# SH10_-_OMAP-L137_JTAG.net
KiCad netlist of a schematic drawn in Altium Designer
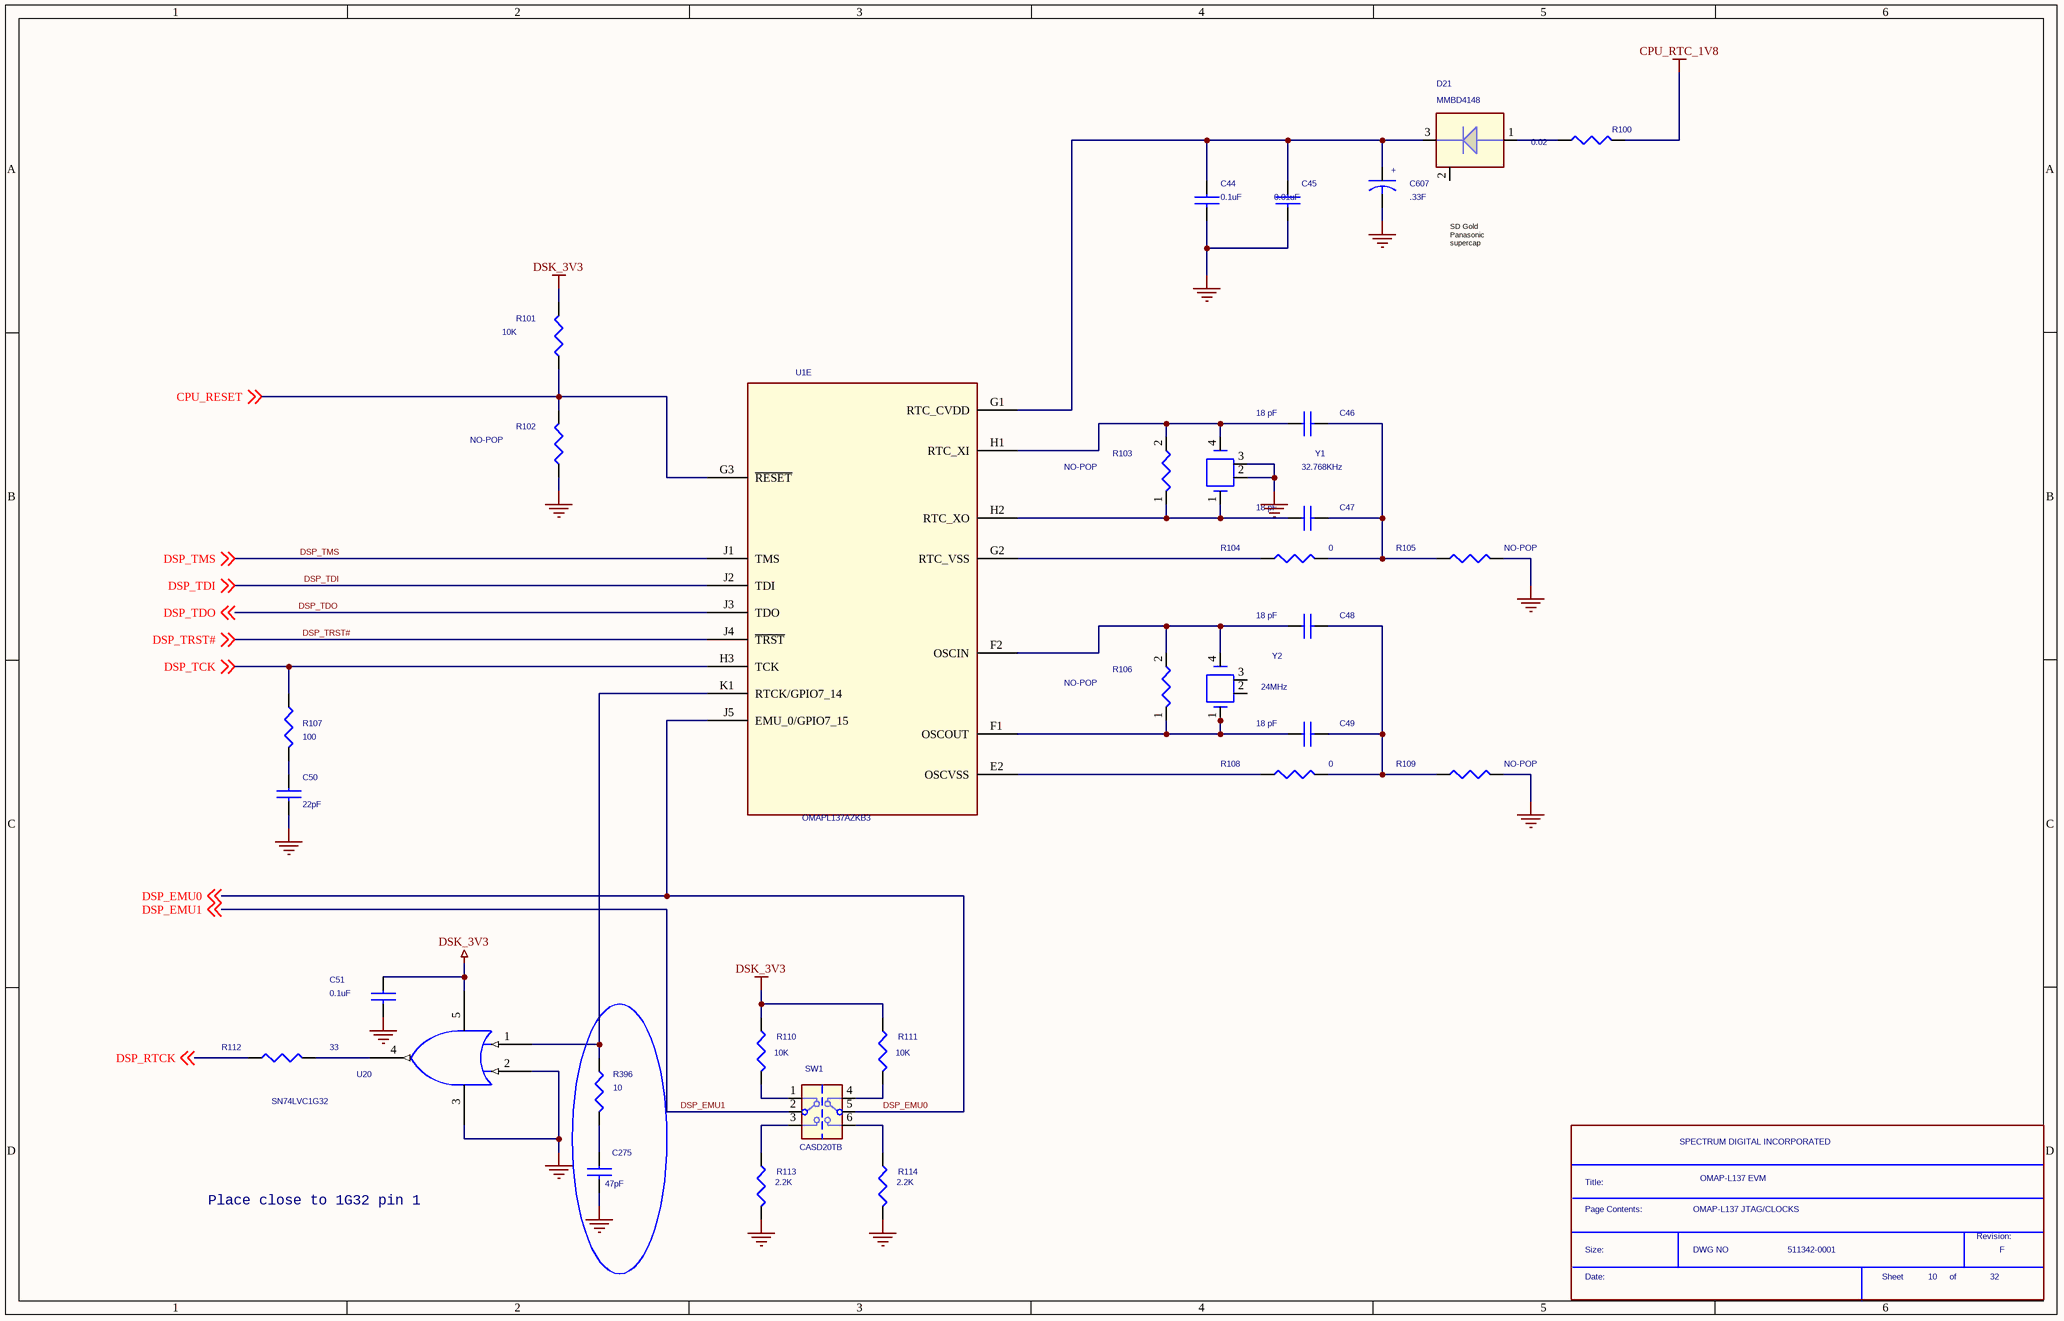
[diagram p0: SH10 - OMAP-L137 JTAG.SchDoc]

(export (version "E")
  (design (tool "Eeschema 10.0.6"))
  (components
    (comp (ref "C44")
      (value "0.1uF")
      (footprint "c402-25")
      (fields (field (name "PART #") "101587-1100R"))
      (libsource (lib "*") (part "CAP NP"))
    )
    (comp (ref "C45")
      (value "0.01uF")
      (footprint "c402-25")
      (fields (field (name "PART #") "101587-1101R"))
      (libsource (lib "*") (part "CAP NP"))
    )
    (comp (ref "C46")
      (value "18 pF")
      (footprint "c603-35x45")
      (fields (field (name "PART #") "101103-1184R"))
      (libsource (lib "*") (part "CAP NP_3"))
    )
    (comp (ref "C47")
      (value "18 pF")
      (footprint "c603-35x45")
      (fields (field (name "PART #") "101103-1184R"))
      (libsource (lib "*") (part "CAP NP_3"))
    )
    (comp (ref "C48")
      (value "18 pF")
      (footprint "c603-35x45")
      (fields (field (name "PART #") "101103-1184R"))
      (libsource (lib "*") (part "CAP NP_3"))
    )
    (comp (ref "C49")
      (value "18 pF")
      (footprint "c603-35x45")
      (fields (field (name "PART #") "101103-1184R"))
      (libsource (lib "*") (part "CAP NP_3"))
    )
    (comp (ref "C50")
      (value "22pF")
      (footprint "c603-35x45")
      (fields (field (name "PART #") "101002-1224R"))
      (libsource (lib "*") (part "CAP NP_7"))
    )
    (comp (ref "C51")
      (value "0.1uF")
      (footprint "c402-25")
      (fields (field (name "PART #") "101587-1100R"))
      (libsource (lib "*") (part "CAP NP"))
    )
    (comp (ref "C275")
      (value "47pF")
      (footprint "C0603")
      (fields (field (name "PART #") "101782-1474R"))
      (libsource (lib "*") (part "CAP .1 uF 10% 0603"))
    )
    (comp (ref "C607")
      (value ".33F")
      (footprint "EIA_D")
      (description ".33F 5.5V Gold SD Horizontal Cap.")
      (fields (field (name "MFR") "Panasonic") (field (name "PART #") "101056-0335R"))
      (libsource (lib "*") (part "CAP_0"))
    )
    (comp (ref "D21")
      (value "MMBD4148")
      (footprint "SOT23-3")
      (fields (field (name "PART #") "100185-0001R"))
      (libsource (lib "*") (part "MMBD4148_0"))
    )
    (comp (ref "R100")
      (value "0.02")
      (footprint "r1206-40x70")
      (fields (field (name "PART #") "102598-0002R"))
      (libsource (lib "*") (part "R"))
    )
    (comp (ref "R101")
      (value "10K")
      (footprint "r402-25")
      (fields (field (name "PART #") "101370-1003R"))
      (libsource (lib "*") (part "R"))
    )
    (comp (ref "R102")
      (value "NO-POP")
      (footprint "r402-25")
      (fields (field (name "PART #") "R0402-NOPOP"))
      (libsource (lib "*") (part "R"))
    )
    (comp (ref "R103")
      (value "NO-POP")
      (footprint "r402-25")
      (fields (field (name "PART #") "R0402-NOPOP"))
      (libsource (lib "*") (part "R_2"))
    )
    (comp (ref "R104")
      (value "0")
      (footprint "r402-25")
      (fields (field (name "PART #") "101370-0001R"))
      (libsource (lib "*") (part "R"))
    )
    (comp (ref "R105")
      (value "NO-POP")
      (footprint "r402-25")
      (fields (field (name "PART #") "R0402-NOPOP"))
      (libsource (lib "*") (part "R"))
    )
    (comp (ref "R106")
      (value "NO-POP")
      (footprint "r402-25")
      (fields (field (name "PART #") "R0402-NOPOP"))
      (libsource (lib "*") (part "R_2"))
    )
    (comp (ref "R107")
      (value "100")
      (footprint "r603-35x45")
      (fields (field (name "PART #") "100642-1001R"))
      (libsource (lib "*") (part "R"))
    )
    (comp (ref "R108")
      (value "0")
      (footprint "r402-25")
      (fields (field (name "PART #") "101370-0001R"))
      (libsource (lib "*") (part "R"))
    )
    (comp (ref "R109")
      (value "NO-POP")
      (footprint "r402-25")
      (fields (field (name "PART #") "R0402-NOPOP"))
      (libsource (lib "*") (part "R"))
    )
    (comp (ref "R110")
      (value "10K")
      (footprint "r402-25")
      (fields (field (name "PART #") "101370-1003R"))
      (libsource (lib "*") (part "R"))
    )
    (comp (ref "R111")
      (value "10K")
      (footprint "r402-25")
      (fields (field (name "PART #") "101370-1003R"))
      (libsource (lib "*") (part "R"))
    )
    (comp (ref "R112")
      (value "33")
      (footprint "r402-25")
      (fields (field (name "PART #") "101370-3300R"))
      (libsource (lib "*") (part "R"))
    )
    (comp (ref "R113")
      (value "2.2K")
      (footprint "r402-25")
      (fields (field (name "PART #") "101370-2202R"))
      (libsource (lib "*") (part "R"))
    )
    (comp (ref "R114")
      (value "2.2K")
      (footprint "r402-25")
      (fields (field (name "PART #") "101370-2202R"))
      (libsource (lib "*") (part "R"))
    )
    (comp (ref "R396")
      (value "10")
      (footprint "r402-25")
      (fields (field (name "PART #") "101370-1000R"))
      (libsource (lib "*") (part "R"))
    )
    (comp (ref "SW1")
      (value "CASD20TB")
      (footprint "sw6-40x67_gw")
      (description "SLIDE Switch, DPDT,  100mA, J HOOK")
      (fields (field (name "MFR") "BC Components") (field (name "PART #") "102181-0002R"))
      (libsource (lib "*") (part "SW - DPDT 5.4x4.2 Slide CAS220A"))
    )
    (comp (ref "U1")
      (value "OMAPL137AZKB3")
      (footprint "skt256-6064")
      (fields (field (name "PART #") "102772-0001"))
      (libsource (lib "*") (part "PRIMUS_BGA_1"))
    )
    (comp (ref "U20")
      (value "SN74LVC1G32")
      (footprint "SO5")
      (fields (field (name "PART #") "101057-0032R"))
      (libsource (lib "*") (part "1G032"))
    )
    (comp (ref "Y1")
      (value "32.768KHz")
      (footprint "xtal4-23x47-ssp-t7")
      (fields (field (name "PART #") "102883-0032R"))
      (libsource (lib "*") (part "CRYSTAL_0"))
    )
    (comp (ref "Y2")
      (value "24MHz")
      (footprint "xtal2-75x94")
      (fields (field (name "PART #") "101590-0240R") (field (name "SPECTRUM PART#") "101590-0270"))
      (libsource (lib "*") (part "CRYSTAL_0"))
    )
  )
  (nets
    (net (code "1") (name "CPU_RESET") (class "Default")
      (node (ref "R101") (pin "2") (pinfunction "2_2") (pintype "passive"))
      (node (ref "R102") (pin "1") (pinfunction "1_1") (pintype "passive"))
      (node (ref "U1") (pin "G3") (pinfunction "~{RESET}_G3") (pintype "passive"))
    )
    (net (code "2") (name "CPU_RTC_1V8") (class "Default")
      (node (ref "R100") (pin "1") (pinfunction "1_1") (pintype "passive"))
    )
    (net (code "3") (name "DSK_3V3") (class "Default")
      (node (ref "C51") (pin "1") (pinfunction "1_1") (pintype "passive"))
      (node (ref "R101") (pin "1") (pinfunction "1_1") (pintype "passive"))
      (node (ref "R110") (pin "1") (pinfunction "1_1") (pintype "passive"))
      (node (ref "R111") (pin "1") (pinfunction "1_1") (pintype "passive"))
      (node (ref "U20") (pin "5") (pinfunction "VCC_5") (pintype "power_in"))
    )
    (net (code "4") (name "DSP_EMU0") (class "Default")
      (node (ref "SW1") (pin "5") (pinfunction "5_5") (pintype "passive"))
      (node (ref "U1") (pin "J5") (pinfunction "EMU_0/GPIO7_15_J5") (pintype "passive"))
    )
    (net (code "5") (name "DSP_EMU1") (class "Default")
      (node (ref "SW1") (pin "2") (pinfunction "2_2") (pintype "passive"))
    )
    (net (code "6") (name "DSP_RTCK") (class "Default")
      (node (ref "R112") (pin "1") (pinfunction "1_1") (pintype "passive"))
    )
    (net (code "7") (name "DSP_TCK") (class "Default")
      (node (ref "R107") (pin "1") (pinfunction "1_1") (pintype "passive"))
      (node (ref "U1") (pin "H3") (pinfunction "TCK_H3") (pintype "passive"))
    )
    (net (code "8") (name "DSP_TDI") (class "Default")
      (node (ref "U1") (pin "J2") (pinfunction "TDI_J2") (pintype "passive"))
    )
    (net (code "9") (name "DSP_TDO") (class "Default")
      (node (ref "U1") (pin "J3") (pinfunction "TDO_J3") (pintype "passive"))
    )
    (net (code "10") (name "DSP_TMS") (class "Default")
      (node (ref "U1") (pin "J1") (pinfunction "TMS_J1") (pintype "passive"))
    )
    (net (code "11") (name "DSP_TRST#") (class "Default")
      (node (ref "U1") (pin "J4") (pinfunction "~{TRST}_J4") (pintype "passive"))
    )
    (net (code "12") (name "GND") (class "Default")
      (node (ref "C275") (pin "2") (pinfunction "2_2") (pintype "passive"))
      (node (ref "C44") (pin "2") (pinfunction "2_2") (pintype "passive"))
      (node (ref "C45") (pin "2") (pinfunction "2_2") (pintype "passive"))
      (node (ref "C50") (pin "2") (pinfunction "2_2") (pintype "passive"))
      (node (ref "C51") (pin "2") (pinfunction "2_2") (pintype "passive"))
      (node (ref "C607") (pin "2") (pinfunction "2_2") (pintype "passive"))
      (node (ref "R102") (pin "2") (pinfunction "2_2") (pintype "passive"))
      (node (ref "R105") (pin "2") (pinfunction "2_2") (pintype "passive"))
      (node (ref "R109") (pin "2") (pinfunction "2_2") (pintype "passive"))
      (node (ref "R113") (pin "2") (pinfunction "2_2") (pintype "passive"))
      (node (ref "R114") (pin "2") (pinfunction "2_2") (pintype "passive"))
      (node (ref "U20") (pin "2") (pinfunction "A_2") (pintype "input"))
      (node (ref "U20") (pin "3") (pinfunction "GND_3") (pintype "power_in"))
      (node (ref "Y1") (pin "2") (pinfunction "2_2") (pintype "passive"))
      (node (ref "Y1") (pin "3") (pinfunction "3_3") (pintype "passive"))
    )
    (net (code "13") (name "Net-(C46-Pad2)") (class "Default")
      (node (ref "C46") (pin "2") (pinfunction "2_2") (pintype "passive"))
      (node (ref "C47") (pin "2") (pinfunction "2_2") (pintype "passive"))
      (node (ref "R104") (pin "2") (pinfunction "2_2") (pintype "passive"))
      (node (ref "R105") (pin "1") (pinfunction "1_1") (pintype "passive"))
    )
    (net (code "14") (name "Net-(C48-Pad2)") (class "Default")
      (node (ref "C48") (pin "2") (pinfunction "2_2") (pintype "passive"))
      (node (ref "C49") (pin "2") (pinfunction "2_2") (pintype "passive"))
      (node (ref "R108") (pin "2") (pinfunction "2_2") (pintype "passive"))
      (node (ref "R109") (pin "1") (pinfunction "1_1") (pintype "passive"))
    )
    (net (code "15") (name "Net-(C50-Pad1)") (class "Default")
      (node (ref "C50") (pin "1") (pinfunction "1_1") (pintype "passive"))
      (node (ref "R107") (pin "2") (pinfunction "2_2") (pintype "passive"))
    )
    (net (code "16") (name "Net-(C275-Pad1)") (class "Default")
      (node (ref "C275") (pin "1") (pinfunction "1_1") (pintype "passive"))
      (node (ref "R396") (pin "2") (pinfunction "2_2") (pintype "passive"))
    )
    (net (code "17") (name "Net-(D21-ANODE)") (class "Default")
      (node (ref "D21") (pin "1") (pinfunction "ANODE_1") (pintype "passive"))
      (node (ref "R100") (pin "2") (pinfunction "2_2") (pintype "passive"))
    )
    (net (code "18") (name "Net-(D21-CATHODE)") (class "Default")
      (node (ref "C44") (pin "1") (pinfunction "1_1") (pintype "passive"))
      (node (ref "C45") (pin "1") (pinfunction "1_1") (pintype "passive"))
      (node (ref "C607") (pin "1") (pinfunction "1_1") (pintype "passive"))
      (node (ref "D21") (pin "3") (pinfunction "CATHODE_3") (pintype "passive"))
      (node (ref "U1") (pin "G1") (pinfunction "RTC_CVDD_G1") (pintype "power_in"))
    )
    (net (code "19") (name "Net-(R110-Pad2)") (class "Default")
      (node (ref "R110") (pin "2") (pinfunction "2_2") (pintype "passive"))
      (node (ref "SW1") (pin "1") (pinfunction "1_1") (pintype "passive"))
    )
    (net (code "20") (name "Net-(R111-Pad2)") (class "Default")
      (node (ref "R111") (pin "2") (pinfunction "2_2") (pintype "passive"))
      (node (ref "SW1") (pin "4") (pinfunction "4_4") (pintype "passive"))
    )
    (net (code "21") (name "Net-(R113-Pad1)") (class "Default")
      (node (ref "R113") (pin "1") (pinfunction "1_1") (pintype "passive"))
      (node (ref "SW1") (pin "3") (pinfunction "3_3") (pintype "passive"))
    )
    (net (code "22") (name "Net-(R114-Pad1)") (class "Default")
      (node (ref "R114") (pin "1") (pinfunction "1_1") (pintype "passive"))
      (node (ref "SW1") (pin "6") (pinfunction "6_6") (pintype "passive"))
    )
    (net (code "23") (name "Net-(U1E-OSCIN)") (class "Default")
      (node (ref "C48") (pin "1") (pinfunction "1_1") (pintype "passive"))
      (node (ref "R106") (pin "2") (pinfunction "2_2") (pintype "passive"))
      (node (ref "U1") (pin "F2") (pinfunction "OSCIN_F2") (pintype "passive"))
      (node (ref "Y2") (pin "4") (pinfunction "4_4") (pintype "passive"))
    )
    (net (code "24") (name "Net-(U1E-OSCOUT)") (class "Default")
      (node (ref "C49") (pin "1") (pinfunction "1_1") (pintype "passive"))
      (node (ref "R106") (pin "1") (pinfunction "1_1") (pintype "passive"))
      (node (ref "U1") (pin "F1") (pinfunction "OSCOUT_F1") (pintype "passive"))
      (node (ref "Y2") (pin "1") (pinfunction "1_1") (pintype "passive"))
    )
    (net (code "25") (name "Net-(U1E-OSCVSS)") (class "Default")
      (node (ref "R108") (pin "1") (pinfunction "1_1") (pintype "passive"))
      (node (ref "U1") (pin "E2") (pinfunction "OSCVSS_E2") (pintype "power_in"))
    )
    (net (code "26") (name "Net-(U1E-RTCK{slash}GPIO7_14)") (class "Default")
      (node (ref "R396") (pin "1") (pinfunction "1_1") (pintype "passive"))
      (node (ref "U1") (pin "K1") (pinfunction "RTCK/GPIO7_14_K1") (pintype "passive"))
      (node (ref "U20") (pin "1") (pinfunction "B_1") (pintype "input"))
    )
    (net (code "27") (name "Net-(U1E-RTC_VSS)") (class "Default")
      (node (ref "R104") (pin "1") (pinfunction "1_1") (pintype "passive"))
      (node (ref "U1") (pin "G2") (pinfunction "RTC_VSS_G2") (pintype "power_in"))
    )
    (net (code "28") (name "Net-(U1E-RTC_XI)") (class "Default")
      (node (ref "C46") (pin "1") (pinfunction "1_1") (pintype "passive"))
      (node (ref "R103") (pin "2") (pinfunction "2_2") (pintype "passive"))
      (node (ref "U1") (pin "H1") (pinfunction "RTC_XI_H1") (pintype "passive"))
      (node (ref "Y1") (pin "4") (pinfunction "4_4") (pintype "passive"))
    )
    (net (code "29") (name "Net-(U1E-RTC_XO)") (class "Default")
      (node (ref "C47") (pin "1") (pinfunction "1_1") (pintype "passive"))
      (node (ref "R103") (pin "1") (pinfunction "1_1") (pintype "passive"))
      (node (ref "U1") (pin "H2") (pinfunction "RTC_XO_H2") (pintype "passive"))
      (node (ref "Y1") (pin "1") (pinfunction "1_1") (pintype "passive"))
    )
    (net (code "30") (name "Net-(U20-Y)") (class "Default")
      (node (ref "R112") (pin "2") (pinfunction "2_2") (pintype "passive"))
      (node (ref "U20") (pin "4") (pinfunction "Y_4") (pintype "output"))
    )
    (net (code "31") (name "unconnected-(D21-Pad2)") (class "Default")
      (node (ref "D21") (pin "2") (pinfunction "2_2") (pintype "passive"))
    )
    (net (code "32") (name "unconnected-(Y2-Pad2)") (class "Default")
      (node (ref "Y2") (pin "2") (pinfunction "2_2") (pintype "passive"))
    )
    (net (code "33") (name "unconnected-(Y2-Pad3)") (class "Default")
      (node (ref "Y2") (pin "3") (pinfunction "3_3") (pintype "passive"))
    )
  )
)
